# Stack_Rduino-SAMD_V2-PRO_2021-01-03_21-2.net
KiCad netlist of a schematic drawn in Altium Designer
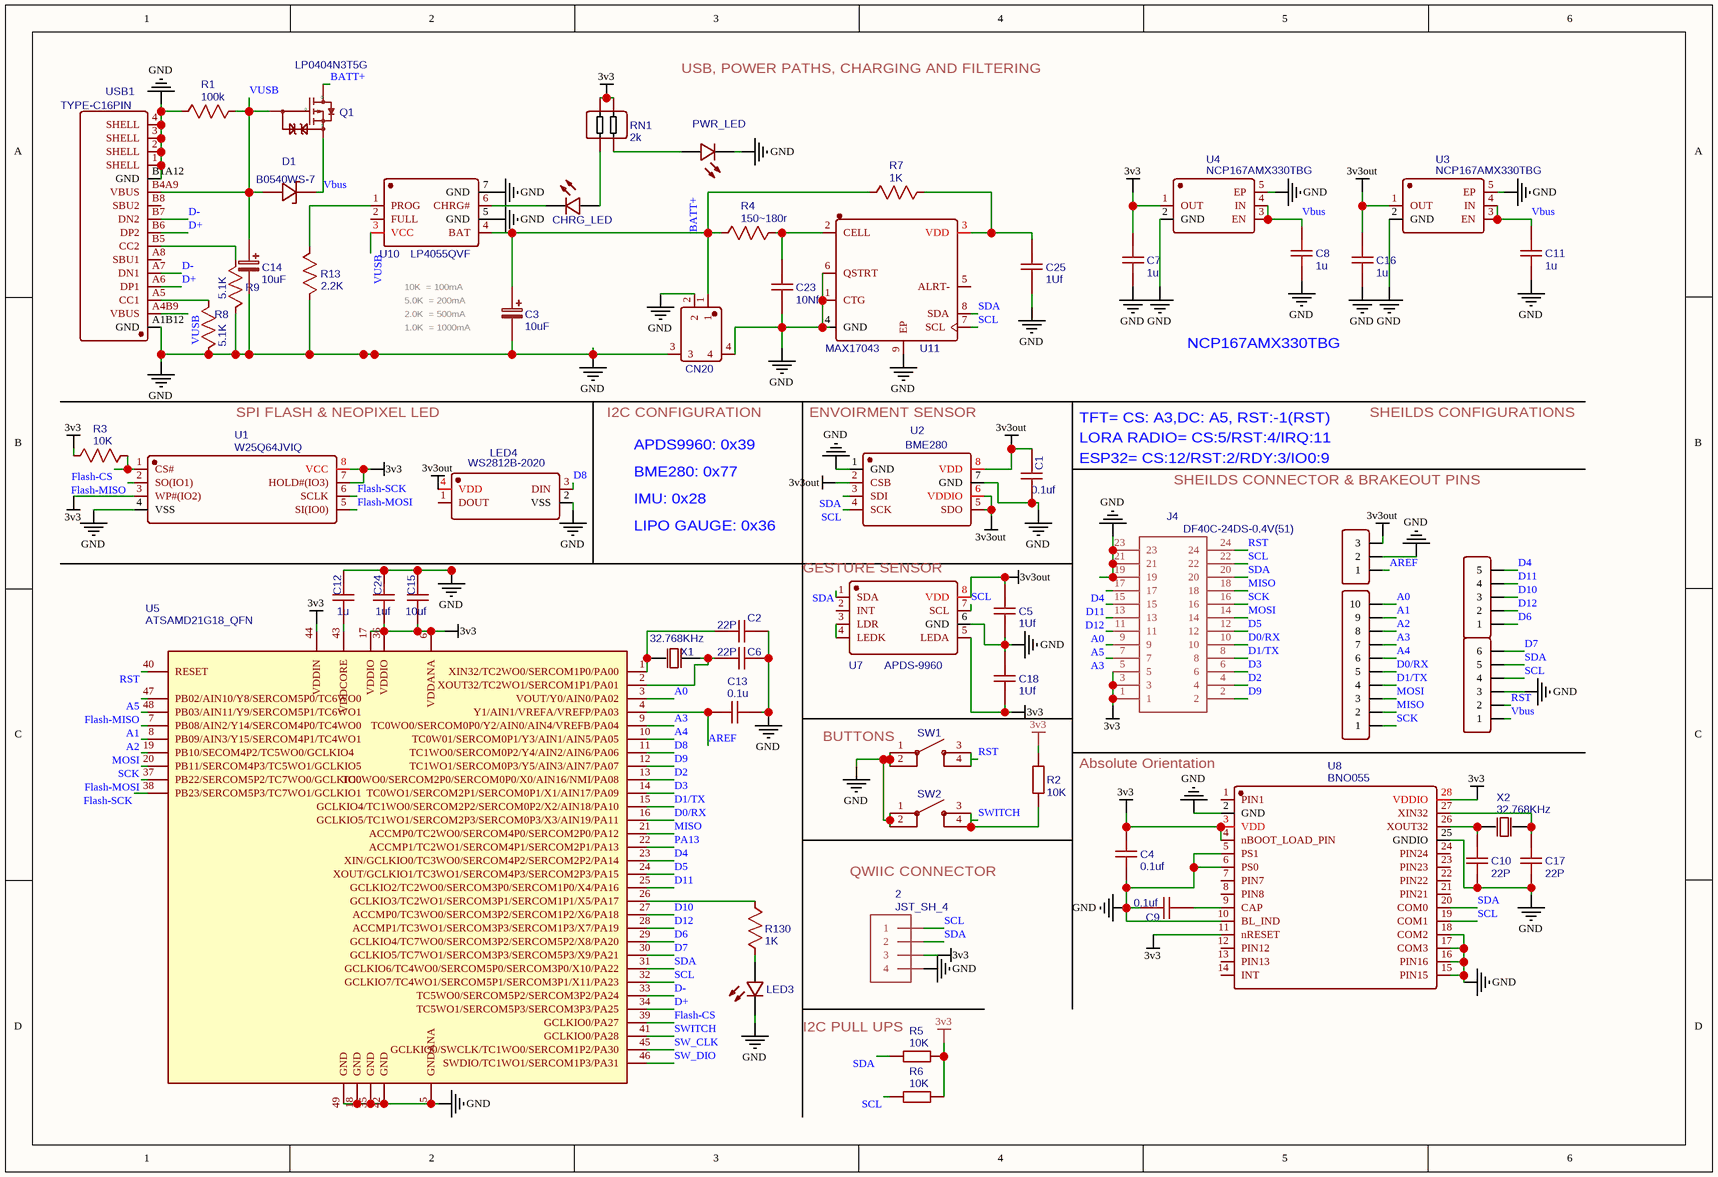
[diagram p0: Stack_Rduino-SAMD_V2-PRO_2021-01-03_21-24-34.schdoc]

(export (version "E")
  (design (tool "Eeschema 10.0.6"))
  (components
    (comp (ref "2")
      (value "JST_SH_4")
      (fields (field (name "CONTRIBUTOR") "guerwood"))
      (libsource (lib "altium-import") (part "root_0_JST_SH_4_"))
    )
    (comp (ref "C1")
      (value "0.1uf")
      (fields (field (name "CONTRIBUTOR") "LCEDA_Lib"))
      (libsource (lib "altium-import") (part "root_3_0.1uf_"))
    )
    (comp (ref "C2")
      (value "22P")
      (fields (field (name "CONTRIBUTOR") "LCEDA_Lib"))
      (libsource (lib "altium-import") (part "root_2_22P_"))
    )
    (comp (ref "C3")
      (value "10uF")
      (fields
        (field (name "BOM_SUPPLIER PART") "C597677")
        (field (name "BOM_MANUFACTURER PART") "TACL106M006XTA")
        (field (name "CONTRIBUTOR") "LCSC")
      )
      (libsource (lib "altium-import") (part "root_1_10uF_"))
    )
    (comp (ref "C4")
      (value "0.1uf")
      (fields (field (name "CONTRIBUTOR") "LCEDA_Lib"))
      (libsource (lib "altium-import") (part "root_1_0.1uf_"))
    )
    (comp (ref "C5")
      (value "1Uf")
      (fields (field (name "CONTRIBUTOR") "LCEDA_Lib"))
      (libsource (lib "altium-import") (part "root_3_1Uf_"))
    )
    (comp (ref "C6")
      (value "22P")
      (fields (field (name "CONTRIBUTOR") "LCEDA_Lib"))
      (libsource (lib "altium-import") (part "root_0_22P_"))
    )
    (comp (ref "C7")
      (value "1u")
      (fields (field (name "CONTRIBUTOR") "LCEDA_Lib"))
      (libsource (lib "altium-import") (part "root_3_1u_"))
    )
    (comp (ref "C8")
      (value "1u")
      (fields (field (name "CONTRIBUTOR") "LCEDA_Lib"))
      (libsource (lib "altium-import") (part "root_3_1u_"))
    )
    (comp (ref "C9")
      (value "0.1uf")
      (fields (field (name "CONTRIBUTOR") "LCEDA_Lib"))
      (libsource (lib "altium-import") (part "root_0_0.1uf_"))
    )
    (comp (ref "C10")
      (value "22P")
      (fields (field (name "CONTRIBUTOR") "LCEDA_Lib"))
      (libsource (lib "altium-import") (part "root_3_22P_"))
    )
    (comp (ref "C11")
      (value "1u")
      (fields (field (name "CONTRIBUTOR") "LCEDA_Lib"))
      (libsource (lib "altium-import") (part "root_3_1u_"))
    )
    (comp (ref "C12")
      (value "1u")
      (fields (field (name "CONTRIBUTOR") "LCEDA_Lib"))
      (libsource (lib "altium-import") (part "root_3_1u_"))
    )
    (comp (ref "C13")
      (value "0.1u")
      (fields (field (name "CONTRIBUTOR") "LCEDA_Lib"))
      (libsource (lib "altium-import") (part "root_2_0.1u_"))
    )
    (comp (ref "C14")
      (value "10uF")
      (fields
        (field (name "BOM_SUPPLIER PART") "C597677")
        (field (name "BOM_MANUFACTURER PART") "TACL106M006XTA")
        (field (name "CONTRIBUTOR") "LCSC")
      )
      (libsource (lib "altium-import") (part "root_1_10uF_"))
    )
    (comp (ref "C15")
      (value "10uf")
      (fields (field (name "CONTRIBUTOR") "LCEDA_Lib"))
      (libsource (lib "altium-import") (part "root_1_10uf_"))
    )
    (comp (ref "C16")
      (value "1u")
      (fields (field (name "CONTRIBUTOR") "LCEDA_Lib"))
      (libsource (lib "altium-import") (part "root_3_1u_"))
    )
    (comp (ref "C17")
      (value "22P")
      (fields (field (name "CONTRIBUTOR") "LCEDA_Lib"))
      (libsource (lib "altium-import") (part "root_1_22P_"))
    )
    (comp (ref "C18")
      (value "1Uf")
      (fields (field (name "CONTRIBUTOR") "LCEDA_Lib"))
      (libsource (lib "altium-import") (part "root_3_1Uf_"))
    )
    (comp (ref "C23")
      (value "10Nf")
      (fields (field (name "CONTRIBUTOR") "LCEDA_Lib"))
      (libsource (lib "altium-import") (part "root_1_10Nf_"))
    )
    (comp (ref "C24")
      (value "1uf")
      (fields (field (name "CONTRIBUTOR") "LCEDA_Lib"))
      (libsource (lib "altium-import") (part "root_1_1uf_"))
    )
    (comp (ref "C25")
      (value "1Uf")
      (fields (field (name "CONTRIBUTOR") "LCEDA_Lib"))
      (libsource (lib "altium-import") (part "root_3_1Uf_"))
    )
    (comp (ref "CHRG_LED")
      (value "Green")
      (fields
        (field (name "BOM_MANUFACTURER PART") "BL-HB337A-AV-TRB")
        (field (name "BOM_SUPPLIER PART") "C165977")
        (field (name "CONTRIBUTOR") "LCSC")
      )
      (libsource (lib "altium-import") (part "root_0_Green_"))
    )
    (comp (ref "CN20")
      (value "A1002WR-S-2P")
      (fields (field (name "BOM_SUPPLIER PART") "C239520") (field (name "CONTRIBUTOR") "LCSC"))
      (libsource (lib "altium-import") (part "root_3_A1002WR-S-2P_"))
    )
    (comp (ref "D1")
      (value "B0540WS-7")
      (fields (field (name "BOM_SUPPLIER PART") "C98664") (field (name "CONTRIBUTOR") "LCSC"))
      (libsource (lib "altium-import") (part "root_2_B0540WS-7_"))
    )
    (comp (ref "H1")
      (value "HDR-F-2.54_1x5")
      (fields (field (name "BOM_SUPPLIER PART") "C50950") (field (name "CONTRIBUTOR") "LCEDA_Lib"))
      (libsource (lib "altium-import") (part "root_2_HDR-F-2.54_1x5_"))
    )
    (comp (ref "H2")
      (value "HDR-F-2.54_1x6")
      (fields (field (name "BOM_SUPPLIER PART") "C40877") (field (name "CONTRIBUTOR") "LCEDA_Lib"))
      (libsource (lib "altium-import") (part "root_2_HDR-F-2.54_1x6_"))
    )
    (comp (ref "H3")
      (value "HDR-F-2.54_1x10")
      (fields (field (name "BOM_SUPPLIER PART") "C35445") (field (name "CONTRIBUTOR") "LCEDA_Lib"))
      (libsource (lib "altium-import") (part "root_2_HDR-F-2.54_1x10_"))
    )
    (comp (ref "J1")
      (value "HDR-M-2.54_1x3")
      (fields (field (name "BOM_SUPPLIER PART") "C180248") (field (name "CONTRIBUTOR") "LCEDA_Lib"))
      (libsource (lib "altium-import") (part "root_2_HDR-M-2.54_1x3_"))
    )
    (comp (ref "J4")
      (value "DF40C-24DS-0.4V(51)")
      (fields (field (name "BOM_SUPPLIER PART") "C424640") (field (name "CONTRIBUTOR") "Hany_elkomy"))
      (libsource (lib "altium-import") (part "root_2_DF40C-24DS-0.4V(51)_"))
    )
    (comp (ref "LED3")
      (value "BL-HB337A-AV-TRB")
      (fields (field (name "BOM_SUPPLIER PART") "C165977") (field (name "CONTRIBUTOR") "LCSC"))
      (libsource (lib "altium-import") (part "root_1_BL-HB337A-AV-TRB_"))
    )
    (comp (ref "LED4")
      (value "WS2812B-2020")
      (fields
        (field (name "BOM_MANUFACTURER PART") "WS2812B")
        (field (name "BOM_SUPPLIER PART") "C114585")
        (field (name "CONTRIBUTOR") "spatz")
      )
      (libsource (lib "altium-import") (part "root_0_WS2812B-2020_"))
    )
    (comp (ref "PWR_LED")
      (value "Red")
      (fields
        (field (name "BOM_MANUFACTURER PART") "BL-HB337A-AV-TRB")
        (field (name "BOM_SUPPLIER PART") "C165977")
        (field (name "CONTRIBUTOR") "LCSC")
      )
      (libsource (lib "altium-import") (part "root_2_Red_"))
    )
    (comp (ref "Q1")
      (value "LP0404N3T5G")
      (fields (field (name "BOM_SUPPLIER PART") "C172433") (field (name "CONTRIBUTOR") "LCSC"))
      (libsource (lib "altium-import") (part "root_0_LP0404N3T5G_"))
    )
    (comp (ref "R1")
      (value "100k")
      (fields (field (name "CONTRIBUTOR") "LCEDA_Lib"))
      (libsource (lib "altium-import") (part "root_0_100k_"))
    )
    (comp (ref "R2")
      (value "10K")
      (fields
        (field (name "BOM_MANUFACTURER PART") "RC0603FR-0739KL")
        (field (name "BOM_SUPPLIER PART") "C163424")
        (field (name "CONTRIBUTOR") "LCSC")
      )
      (libsource (lib "altium-import") (part "root_3_10K_"))
    )
    (comp (ref "R3")
      (value "10K")
      (fields (field (name "CONTRIBUTOR") "LCEDA_Lib"))
      (libsource (lib "") (part "root_2_10K__1"))
    )
    (comp (ref "R4")
      (value "150~180r")
      (fields (field (name "CONTRIBUTOR") "LCEDA_Lib"))
      (libsource (lib "altium-import") (part "root_2_150~180r_"))
    )
    (comp (ref "R5")
      (value "10K")
      (fields
        (field (name "BOM_MANUFACTURER PART") "RC0603FR-0739KL")
        (field (name "BOM_SUPPLIER PART") "C163424")
        (field (name "CONTRIBUTOR") "LCSC")
      )
      (libsource (lib "altium-import") (part "root_2_10K_"))
    )
    (comp (ref "R6")
      (value "10K")
      (fields
        (field (name "BOM_MANUFACTURER PART") "RC0603FR-0739KL")
        (field (name "BOM_SUPPLIER PART") "C163424")
        (field (name "CONTRIBUTOR") "LCSC")
      )
      (libsource (lib "altium-import") (part "root_0_10K_"))
    )
    (comp (ref "R7")
      (value "1K")
      (fields (field (name "CONTRIBUTOR") "LCEDA_Lib"))
      (libsource (lib "altium-import") (part "root_2_1K_"))
    )
    (comp (ref "R8")
      (value "5.1K")
      (fields (field (name "CONTRIBUTOR") "LCEDA_Lib"))
      (libsource (lib "altium-import") (part "root_3_5.1K_"))
    )
    (comp (ref "R9")
      (value "5.1K")
      (fields (field (name "CONTRIBUTOR") "LCEDA_Lib"))
      (libsource (lib "altium-import") (part "root_1_5.1K_"))
    )
    (comp (ref "R13")
      (value "2.2K")
      (fields (field (name "CONTRIBUTOR") "LCEDA_Lib"))
      (libsource (lib "altium-import") (part "root_3_2.2K_"))
    )
    (comp (ref "R130")
      (value "1K")
      (fields (field (name "CONTRIBUTOR") "LCEDA_Lib"))
      (libsource (lib "altium-import") (part "root_3_1K_"))
    )
    (comp (ref "RN1")
      (value "2k")
      (fields
        (field (name "BOM_SUPPLIER PART") "C718251")
        (field (name "BOM_MANUFACTURER PART") "YC122-JR-072K")
        (field (name "CONTRIBUTOR") "LCSC")
      )
      (libsource (lib "altium-import") (part "root_3_2k_"))
    )
    (comp (ref "SW1")
      (value "K2-1177SW-D4DW-06-hany")
      (fields
        (field (name "BOM_SUPPLIER PART") "C223820")
        (field (name "BOM_MANUFACTURER PART") "K2-1177SW-D4DW-06")
        (field (name "CONTRIBUTOR") "Hany_elkomy")
      )
      (libsource (lib "altium-import") (part "root_0_K2-1177SW-D4DW-06-hany_"))
    )
    (comp (ref "SW2")
      (value "K2-1177SW-D4DW-06-hany")
      (fields
        (field (name "BOM_SUPPLIER PART") "C223820")
        (field (name "BOM_MANUFACTURER PART") "K2-1177SW-D4DW-06")
        (field (name "CONTRIBUTOR") "Hany_elkomy")
      )
      (libsource (lib "altium-import") (part "root_0_K2-1177SW-D4DW-06-hany_"))
    )
    (comp (ref "U1")
      (value "W25Q64JVIQ")
      (fields
        (field (name "BOM_SUPPLIER PART") "C395538")
        (field (name "BOM_MANUFACTURER PART") "GD25Q64CQIGR")
        (field (name "CONTRIBUTOR") "LCSC")
      )
      (libsource (lib "altium-import") (part "root_0_W25Q64JVIQ_"))
    )
    (comp (ref "U2")
      (value "BME280")
      (fields (field (name "BOM_SUPPLIER PART") "C92489") (field (name "CONTRIBUTOR") "LCSC"))
      (libsource (lib "altium-import") (part "root_0_BME280_"))
    )
    (comp (ref "U3")
      (value "NCP167AMX330TBG")
      (fields
        (field (name "BOM_MANUFACTURER PART") "NCP170AMX300TCG")
        (field (name "BOM_SUPPLIER PART") "C152284")
        (field (name "CONTRIBUTOR") "LCSC")
      )
      (libsource (lib "altium-import") (part "root_0_NCP167AMX330TBG_"))
    )
    (comp (ref "U4")
      (value "NCP167AMX330TBG")
      (fields
        (field (name "BOM_MANUFACTURER PART") "NCP170AMX300TCG")
        (field (name "BOM_SUPPLIER PART") "C152284")
        (field (name "CONTRIBUTOR") "LCSC")
      )
      (libsource (lib "altium-import") (part "root_0_NCP167AMX330TBG_"))
    )
    (comp (ref "U5")
      (value "ATSAMD21G18_QFN")
      (fields (field (name "CONTRIBUTOR") "corlovsky"))
      (libsource (lib "altium-import") (part "root_0_ATSAMD21G18_QFN_"))
    )
    (comp (ref "U7")
      (value "APDS-9960")
      (fields (field (name "BOM_SUPPLIER PART") "C93222") (field (name "CONTRIBUTOR") "LCSC"))
      (libsource (lib "altium-import") (part "root_0_APDS-9960_"))
    )
    (comp (ref "U8")
      (value "BNO055")
      (fields (field (name "BOM_SUPPLIER PART") "C93216") (field (name "CONTRIBUTOR") "LCSC"))
      (libsource (lib "altium-import") (part "root_0_BNO055_"))
    )
    (comp (ref "U10")
      (value "LP4055QVF")
      (fields (field (name "BOM_SUPPLIER PART") "C387714") (field (name "CONTRIBUTOR") "LCSC"))
      (libsource (lib "altium-import") (part "root_0_LP4055QVF_"))
    )
    (comp (ref "U11")
      (value "MAX17043")
      (fields (field (name "BOM_MANUFACTURER PART") "MAX17043G+U") (field (name "CONTRIBUTOR") "whatski"))
      (libsource (lib "altium-import") (part "root_0_MAX17043_"))
    )
    (comp (ref "USB1")
      (value "TYPE-C16PIN")
      (fields (field (name "BOM_SUPPLIER PART") "C393939") (field (name "CONTRIBUTOR") "LCSC"))
      (libsource (lib "altium-import") (part "root_2_TYPE-C16PIN_"))
    )
    (comp (ref "X1")
      (value "32.768KHz")
      (fields
        (field (name "BOM_MANUFACTURER PART") "FC-12M32.768KHZ7PF20PPM")
        (field (name "BOM_SUPPLIER PART") "C99009")
      )
      (libsource (lib "altium-import") (part "root_0_32.768KHz_"))
    )
    (comp (ref "X2")
      (value "32.768KHz")
      (fields
        (field (name "BOM_MANUFACTURER PART") "FC-12M32.768KHZ7PF20PPM")
        (field (name "BOM_SUPPLIER PART") "C99009")
      )
      (libsource (lib "altium-import") (part "root_0_32.768KHz_"))
    )
  )
  (nets
    (net (code "1") (name "/A0") (class "Default")
      (node (ref "H3") (pin "10") (pinfunction "10_10") (pintype "passive"))
      (node (ref "J4") (pin "11") (pinfunction "11_11") (pintype "passive"))
      (node (ref "U5") (pin "3") (pinfunction "VOUT/Y0/AIN0/PA02_3") (pintype "passive"))
    )
    (net (code "2") (name "/A1") (class "Default")
      (node (ref "H3") (pin "9") (pinfunction "9_9") (pintype "passive"))
      (node (ref "U5") (pin "7") (pinfunction "PB08/AIN2/Y14/SERCOM4P0/TC4WO0_7") (pintype "passive"))
    )
    (net (code "3") (name "/A2") (class "Default")
      (node (ref "H3") (pin "8") (pinfunction "8_8") (pintype "passive"))
      (node (ref "U5") (pin "8") (pinfunction "PB09/AIN3/Y15/SERCOM4P1/TC4WO1_8") (pintype "passive"))
    )
    (net (code "4") (name "/A3") (class "Default")
      (node (ref "H3") (pin "7") (pinfunction "7_7") (pintype "passive"))
      (node (ref "J4") (pin "7") (pinfunction "7_7") (pintype "passive"))
      (node (ref "U5") (pin "9") (pinfunction "TC0WO0/SERCOM0P0/Y2/AIN0/AIN4/VREFB/PA04_9") (pintype "passive"))
    )
    (net (code "5") (name "/A4") (class "Default")
      (node (ref "H3") (pin "6") (pinfunction "6_6") (pintype "passive"))
      (node (ref "U5") (pin "10") (pinfunction "TC0W01/SERCOM0P1/Y3/AIN1/AIN5/PA05_10") (pintype "passive"))
    )
    (net (code "6") (name "/A5") (class "Default")
      (node (ref "J4") (pin "9") (pinfunction "9_9") (pintype "passive"))
      (node (ref "U5") (pin "47") (pinfunction "PB02/AIN10/Y8/SERCOM5P0/TC6WO0_47") (pintype "passive"))
    )
    (net (code "7") (name "/AREF") (class "Default")
      (node (ref "C13") (pin "2") (pinfunction "2_2") (pintype "passive"))
      (node (ref "J1") (pin "1") (pinfunction "1_1") (pintype "passive"))
      (node (ref "U5") (pin "4") (pinfunction "Y1/AIN1/VREFA/VREFP/PA03_4") (pintype "passive"))
    )
    (net (code "8") (name "/BATT+") (class "Default")
      (node (ref "C3") (pin "1") (pinfunction "1_1") (pintype "passive"))
      (node (ref "CN20") (pin "1") (pinfunction "1_1") (pintype "passive"))
      (node (ref "Q1") (pin "3") (pinfunction "D_3") (pintype "passive"))
      (node (ref "R4") (pin "2") (pinfunction "2_2") (pintype "passive"))
      (node (ref "R7") (pin "2") (pinfunction "2_2") (pintype "passive"))
      (node (ref "U10") (pin "4") (pinfunction "BAT_4") (pintype "passive"))
    )
    (net (code "9") (name "/D+") (class "Default")
      (node (ref "U5") (pin "34") (pinfunction "TC5WO1/SERCOM5P3/SERCOM3P3/PA25_34") (pintype "passive"))
      (node (ref "USB1") (pin "A6") (pinfunction "DP1_A6") (pintype "passive"))
      (node (ref "USB1") (pin "B6") (pinfunction "DP2_B6") (pintype "passive"))
    )
    (net (code "10") (name "/D-") (class "Default")
      (node (ref "U5") (pin "33") (pinfunction "TC5WO0/SERCOM5P2/SERCOM3P2/PA24_33") (pintype "passive"))
      (node (ref "USB1") (pin "A7") (pinfunction "DN1_A7") (pintype "passive"))
      (node (ref "USB1") (pin "B7") (pinfunction "DN2_B7") (pintype "passive"))
    )
    (net (code "11") (name "/D0{slash}RX") (class "Default")
      (node (ref "H3") (pin "5") (pinfunction "5_5") (pintype "passive"))
      (node (ref "J4") (pin "10") (pinfunction "10_10") (pintype "passive"))
      (node (ref "U5") (pin "16") (pinfunction "GCLKIO5/TC1WO1/SERCOM2P3/SERCOM0P3/X3/AIN19/PA11_16") (pintype "passive"))
    )
    (net (code "12") (name "/D1{slash}TX") (class "Default")
      (node (ref "H3") (pin "4") (pinfunction "4_4") (pintype "passive"))
      (node (ref "J4") (pin "8") (pinfunction "8_8") (pintype "passive"))
      (node (ref "U5") (pin "15") (pinfunction "GCLKIO4/TC1WO0/SERCOM2P2/SERCOM0P2/X2/AIN18/PA10_15") (pintype "passive"))
    )
    (net (code "13") (name "/D2") (class "Default")
      (node (ref "J4") (pin "4") (pinfunction "4_4") (pintype "passive"))
      (node (ref "U5") (pin "13") (pinfunction "TC0WO0/SERCOM2P0/SERCOM0P0/X0/AIN16/NMI/PA08_13") (pintype "passive"))
    )
    (net (code "14") (name "/D3") (class "Default")
      (node (ref "J4") (pin "6") (pinfunction "6_6") (pintype "passive"))
      (node (ref "U5") (pin "14") (pinfunction "TC0WO1/SERCOM2P1/SERCOM0P1/X1/AIN17/PA09_14") (pintype "passive"))
    )
    (net (code "15") (name "/D4") (class "Default")
      (node (ref "H1") (pin "5") (pinfunction "5_5") (pintype "passive"))
      (node (ref "J4") (pin "17") (pinfunction "17_17") (pintype "passive"))
      (node (ref "U5") (pin "23") (pinfunction "XIN/GCLKIO0/TC3WO0/SERCOM4P2/SERCOM2P2/PA14_23") (pintype "passive"))
    )
    (net (code "16") (name "/D5") (class "Default")
      (node (ref "J4") (pin "12") (pinfunction "12_12") (pintype "passive"))
      (node (ref "U5") (pin "24") (pinfunction "XOUT/GCLKIO1/TC3WO1/SERCOM4P3/SERCOM2P3/PA15_24") (pintype "passive"))
    )
    (net (code "17") (name "/D6") (class "Default")
      (node (ref "H1") (pin "1") (pinfunction "1_1") (pintype "passive"))
      (node (ref "U5") (pin "29") (pinfunction "GCLKIO4/TC7WO0/SERCOM3P2/SERCOM5P2/X8/PA20_29") (pintype "passive"))
    )
    (net (code "18") (name "/D7") (class "Default")
      (node (ref "H2") (pin "6") (pinfunction "6_6") (pintype "passive"))
      (node (ref "U5") (pin "30") (pinfunction "GCLKIO5/TC7WO1/SERCOM3P3/SERCOM5P3/X9/PA21_30") (pintype "passive"))
    )
    (net (code "19") (name "/D8") (class "Default")
      (node (ref "LED4") (pin "3") (pinfunction "DIN_3") (pintype "passive"))
      (node (ref "U5") (pin "11") (pinfunction "TC1WO0/SERCOM0P2/Y4/AIN2/AIN6/PA06_11") (pintype "passive"))
    )
    (net (code "20") (name "/D9") (class "Default")
      (node (ref "J4") (pin "2") (pinfunction "2_2") (pintype "passive"))
      (node (ref "U5") (pin "12") (pinfunction "TC1WO1/SERCOM0P3/Y5/AIN3/AIN7/PA07_12") (pintype "passive"))
    )
    (net (code "21") (name "/D10") (class "Default")
      (node (ref "H1") (pin "3") (pinfunction "3_3") (pintype "passive"))
      (node (ref "U5") (pin "27") (pinfunction "ACCMP0/TC3WO0/SERCOM3P2/SERCOM1P2/X6/PA18_27") (pintype "passive"))
    )
    (net (code "22") (name "/D11") (class "Default")
      (node (ref "H1") (pin "4") (pinfunction "4_4") (pintype "passive"))
      (node (ref "J4") (pin "15") (pinfunction "15_15") (pintype "passive"))
      (node (ref "U5") (pin "25") (pinfunction "GCLKIO2/TC2WO0/SERCOM3P0/SERCOM1P0/X4/PA16_25") (pintype "passive"))
    )
    (net (code "23") (name "/D12") (class "Default")
      (node (ref "H1") (pin "2") (pinfunction "2_2") (pintype "passive"))
      (node (ref "J4") (pin "13") (pinfunction "13_13") (pintype "passive"))
      (node (ref "U5") (pin "28") (pinfunction "ACCMP1/TC3WO1/SERCOM3P3/SERCOM1P3/X7/PA19_28") (pintype "passive"))
    )
    (net (code "24") (name "/Flash-CS") (class "Default")
      (node (ref "R3") (pin "1") (pinfunction "1_1") (pintype "passive"))
      (node (ref "U1") (pin "1") (pinfunction "CS#_1") (pintype "passive"))
      (node (ref "U5") (pin "39") (pinfunction "GCLKIO0/PA27_39") (pintype "passive"))
    )
    (net (code "25") (name "/Flash-MISO") (class "Default")
      (node (ref "U1") (pin "2") (pinfunction "SO(IO1)_2") (pintype "passive"))
      (node (ref "U5") (pin "48") (pinfunction "PB03/AIN11/Y9/SERCOM5P1/TC6WO1_48") (pintype "passive"))
    )
    (net (code "26") (name "/Flash-MOSI") (class "Default")
      (node (ref "U1") (pin "5") (pinfunction "SI(IO0)_5") (pintype "passive"))
      (node (ref "U5") (pin "37") (pinfunction "PB22/SERCOM5P2/TC7WO0/GCLKIO0_37") (pintype "passive"))
    )
    (net (code "27") (name "/Flash-SCK") (class "Default")
      (node (ref "U1") (pin "6") (pinfunction "SCLK_6") (pintype "passive"))
      (node (ref "U5") (pin "38") (pinfunction "PB23/SERCOM5P3/TC7WO1/GCLKIO1_38") (pintype "passive"))
    )
    (net (code "28") (name "/MISO") (class "Default")
      (node (ref "H3") (pin "2") (pinfunction "2_2") (pintype "passive"))
      (node (ref "J4") (pin "18") (pinfunction "18_18") (pintype "passive"))
      (node (ref "U5") (pin "21") (pinfunction "ACCMP0/TC2WO0/SERCOM4P0/SERCOM2P0/PA12_21") (pintype "passive"))
    )
    (net (code "29") (name "/MOSI") (class "Default")
      (node (ref "H3") (pin "3") (pinfunction "3_3") (pintype "passive"))
      (node (ref "J4") (pin "14") (pinfunction "14_14") (pintype "passive"))
      (node (ref "U5") (pin "19") (pinfunction "PB10/SECOM4P2/TC5WO0/GCLKIO4_19") (pintype "passive"))
    )
    (net (code "30") (name "/PA13") (class "Default")
      (node (ref "U5") (pin "22") (pinfunction "ACCMP1/TC2WO1/SERCOM4P1/SERCOM2P1/PA13_22") (pintype "passive"))
    )
    (net (code "31") (name "/RST") (class "Default")
      (node (ref "H2") (pin "2") (pinfunction "2_2") (pintype "passive"))
      (node (ref "J4") (pin "24") (pinfunction "24_24") (pintype "passive"))
      (node (ref "SW1") (pin "3") (pinfunction "3_3") (pintype "passive"))
      (node (ref "SW1") (pin "4") (pinfunction "4_4") (pintype "passive"))
      (node (ref "U5") (pin "40") (pinfunction "RESET_40") (pintype "passive"))
    )
    (net (code "32") (name "/SCK") (class "Default")
      (node (ref "H3") (pin "1") (pinfunction "1_1") (pintype "passive"))
      (node (ref "J4") (pin "16") (pinfunction "16_16") (pintype "passive"))
      (node (ref "U5") (pin "20") (pinfunction "PB11/SERCOM4P3/TC5WO1/GCLKIO5_20") (pintype "passive"))
    )
    (net (code "33") (name "/SCL") (class "Default")
      (node (ref "2") (pin "1") (pinfunction "1_1") (pintype "passive"))
      (node (ref "H2") (pin "4") (pinfunction "4_4") (pintype "passive"))
      (node (ref "J4") (pin "22") (pinfunction "22_22") (pintype "passive"))
      (node (ref "R6") (pin "1") (pinfunction "1_1") (pintype "passive"))
      (node (ref "U11") (pin "7") (pinfunction "SCL_7") (pintype "passive"))
      (node (ref "U2") (pin "4") (pinfunction "SCK_4") (pintype "passive"))
      (node (ref "U5") (pin "32") (pinfunction "GCLKIO7/TC4WO1/SERCOM5P1/SERCOM3P1/X11/PA23_32") (pintype "passive"))
      (node (ref "U7") (pin "7") (pinfunction "SCL_7") (pintype "passive"))
      (node (ref "U8") (pin "19") (pinfunction "COM1_19") (pintype "passive"))
    )
    (net (code "34") (name "/SDA") (class "Default")
      (node (ref "2") (pin "2") (pinfunction "2_2") (pintype "passive"))
      (node (ref "H2") (pin "5") (pinfunction "5_5") (pintype "passive"))
      (node (ref "J4") (pin "20") (pinfunction "20_20") (pintype "passive"))
      (node (ref "R5") (pin "2") (pinfunction "2_2") (pintype "passive"))
      (node (ref "U11") (pin "8") (pinfunction "SDA_8") (pintype "passive"))
      (node (ref "U2") (pin "3") (pinfunction "SDI_3") (pintype "passive"))
      (node (ref "U5") (pin "31") (pinfunction "GCLKIO6/TC4WO0/SERCOM5P0/SERCOM3P0/X10/PA22_31") (pintype "passive"))
      (node (ref "U7") (pin "1") (pinfunction "SDA_1") (pintype "passive"))
      (node (ref "U8") (pin "20") (pinfunction "COM0_20") (pintype "passive"))
    )
    (net (code "35") (name "/SWITCH") (class "Default")
      (node (ref "R2") (pin "2") (pinfunction "2_2") (pintype "passive"))
      (node (ref "SW2") (pin "3") (pinfunction "3_3") (pintype "passive"))
      (node (ref "SW2") (pin "4") (pinfunction "4_4") (pintype "passive"))
      (node (ref "U5") (pin "41") (pinfunction "GCLKIO0/PA28_41") (pintype "passive"))
    )
    (net (code "36") (name "/SW_CLK") (class "Default")
      (node (ref "U5") (pin "45") (pinfunction "GCLKIO0/SWCLK/TC1WO0/SERCOM1P2/PA30_45") (pintype "passive"))
    )
    (net (code "37") (name "/SW_DIO") (class "Default")
      (node (ref "U5") (pin "46") (pinfunction "SWDIO/TC1WO1/SERCOM1P3/PA31_46") (pintype "passive"))
    )
    (net (code "38") (name "/VUSB") (class "Default")
      (node (ref "C14") (pin "1") (pinfunction "1_1") (pintype "passive"))
      (node (ref "D1") (pin "2") (pinfunction "A_2") (pintype "passive"))
      (node (ref "Q1") (pin "1") (pinfunction "G_1") (pintype "passive"))
      (node (ref "R1") (pin "2") (pinfunction "2_2") (pintype "passive"))
      (node (ref "U10") (pin "3") (pinfunction "VCC_3") (pintype "passive"))
      (node (ref "USB1") (pin "A4B9") (pinfunction "VBUS_A4B9") (pintype "passive"))
      (node (ref "USB1") (pin "B4A9") (pinfunction "VBUS_B4A9") (pintype "passive"))
    )
    (net (code "39") (name "/Vbus") (class "Default")
      (node (ref "C11") (pin "1") (pinfunction "1_1") (pintype "passive"))
      (node (ref "C8") (pin "1") (pinfunction "1_1") (pintype "passive"))
      (node (ref "D1") (pin "1") (pinfunction "C_1") (pintype "passive"))
      (node (ref "H2") (pin "1") (pinfunction "1_1") (pintype "passive"))
      (node (ref "Q1") (pin "2") (pinfunction "S_2") (pintype "passive"))
      (node (ref "U3") (pin "3") (pinfunction "EN_3") (pintype "passive"))
      (node (ref "U3") (pin "4") (pinfunction "IN_4") (pintype "passive"))
      (node (ref "U4") (pin "3") (pinfunction "EN_3") (pintype "passive"))
      (node (ref "U4") (pin "4") (pinfunction "IN_4") (pintype "passive"))
    )
    (net (code "40") (name "3v3") (class "Default")
      (node (ref "2") (pin "3") (pinfunction "3_3") (pintype "passive"))
      (node (ref "C15") (pin "1") (pinfunction "1_1") (pintype "passive"))
      (node (ref "C18") (pin "2") (pinfunction "2_2") (pintype "passive"))
      (node (ref "C24") (pin "1") (pinfunction "1_1") (pintype "passive"))
      (node (ref "C4") (pin "2") (pinfunction "2_2") (pintype "passive"))
      (node (ref "C7") (pin "1") (pinfunction "1_1") (pintype "passive"))
      (node (ref "J4") (pin "1") (pinfunction "1_1") (pintype "passive"))
      (node (ref "J4") (pin "3") (pinfunction "3_3") (pintype "passive"))
      (node (ref "J4") (pin "5") (pinfunction "5_5") (pintype "passive"))
      (node (ref "R2") (pin "1") (pinfunction "1_1") (pintype "passive"))
      (node (ref "R3") (pin "2") (pinfunction "2_2") (pintype "passive"))
      (node (ref "R5") (pin "1") (pinfunction "1_1") (pintype "passive"))
      (node (ref "R6") (pin "2") (pinfunction "2_2") (pintype "passive"))
      (node (ref "RN1") (pin "1") (pinfunction "1_1") (pintype "passive"))
      (node (ref "RN1") (pin "2") (pinfunction "2_2") (pintype "passive"))
      (node (ref "U1") (pin "3") (pinfunction "WP#(IO2)_3") (pintype "passive"))
      (node (ref "U1") (pin "7") (pinfunction "HOLD#(IO3)_7") (pintype "passive"))
      (node (ref "U1") (pin "8") (pinfunction "VCC_8") (pintype "passive"))
      (node (ref "U4") (pin "1") (pinfunction "OUT_1") (pintype "passive"))
      (node (ref "U5") (pin "17") (pinfunction "VDDIO_17") (pintype "passive"))
      (node (ref "U5") (pin "36") (pinfunction "VDDIO_36") (pintype "passive"))
      (node (ref "U5") (pin "44") (pinfunction "VDDIN_44") (pintype "passive"))
      (node (ref "U5") (pin "6") (pinfunction "VDDANA_6") (pintype "passive"))
      (node (ref "U7") (pin "5") (pinfunction "LEDA_5") (pintype "passive"))
      (node (ref "U8") (pin "11") (pinfunction "nRESET_11") (pintype "passive"))
      (node (ref "U8") (pin "28") (pinfunction "VDDIO_28") (pintype "passive"))
      (node (ref "U8") (pin "3") (pinfunction "VDD_3") (pintype "passive"))
      (node (ref "U8") (pin "4") (pinfunction "nBOOT_LOAD_PIN_4") (pintype "passive"))
    )
    (net (code "41") (name "3v3out") (class "Default")
      (node (ref "C1") (pin "1") (pinfunction "1_1") (pintype "passive"))
      (node (ref "C16") (pin "1") (pinfunction "1_1") (pintype "passive"))
      (node (ref "C5") (pin "1") (pinfunction "1_1") (pintype "passive"))
      (node (ref "J1") (pin "3") (pinfunction "3_3") (pintype "passive"))
      (node (ref "LED4") (pin "4") (pinfunction "VDD_4") (pintype "passive"))
      (node (ref "U2") (pin "2") (pinfunction "CSB_2") (pintype "passive"))
      (node (ref "U2") (pin "5") (pinfunction "SDO_5") (pintype "passive"))
      (node (ref "U2") (pin "6") (pinfunction "VDDIO_6") (pintype "passive"))
      (node (ref "U2") (pin "8") (pinfunction "VDD_8") (pintype "passive"))
      (node (ref "U3") (pin "1") (pinfunction "OUT_1") (pintype "passive"))
      (node (ref "U7") (pin "8") (pinfunction "VDD_8") (pintype "passive"))
    )
    (net (code "42") (name "GND") (class "Default")
      (node (ref "2") (pin "4") (pinfunction "4_4") (pintype "passive"))
      (node (ref "C1") (pin "2") (pinfunction "2_2") (pintype "passive"))
      (node (ref "C10") (pin "2") (pinfunction "2_2") (pintype "passive"))
      (node (ref "C11") (pin "2") (pinfunction "2_2") (pintype "passive"))
      (node (ref "C12") (pin "1") (pinfunction "1_1") (pintype "passive"))
      (node (ref "C13") (pin "1") (pinfunction "1_1") (pintype "passive"))
      (node (ref "C14") (pin "2") (pinfunction "2_2") (pintype "passive"))
      (node (ref "C15") (pin "2") (pinfunction "2_2") (pintype "passive"))
      (node (ref "C16") (pin "2") (pinfunction "2_2") (pintype "passive"))
      (node (ref "C17") (pin "1") (pinfunction "1_1") (pintype "passive"))
      (node (ref "C18") (pin "1") (pinfunction "1_1") (pintype "passive"))
      (node (ref "C2") (pin "1") (pinfunction "1_1") (pintype "passive"))
      (node (ref "C23") (pin "1") (pinfunction "1_1") (pintype "passive"))
      (node (ref "C24") (pin "2") (pinfunction "2_2") (pintype "passive"))
      (node (ref "C25") (pin "2") (pinfunction "2_2") (pintype "passive"))
      (node (ref "C3") (pin "2") (pinfunction "2_2") (pintype "passive"))
      (node (ref "C4") (pin "1") (pinfunction "1_1") (pintype "passive"))
      (node (ref "C5") (pin "2") (pinfunction "2_2") (pintype "passive"))
      (node (ref "C6") (pin "2") (pinfunction "2_2") (pintype "passive"))
      (node (ref "C7") (pin "2") (pinfunction "2_2") (pintype "passive"))
      (node (ref "C8") (pin "2") (pinfunction "2_2") (pintype "passive"))
      (node (ref "C9") (pin "1") (pinfunction "1_1") (pintype "passive"))
      (node (ref "CN20") (pin "2") (pinfunction "2_2") (pintype "passive"))
      (node (ref "CN20") (pin "3") (pinfunction "3_3") (pintype "passive"))
      (node (ref "CN20") (pin "4") (pinfunction "4_4") (pintype "passive"))
      (node (ref "H2") (pin "3") (pinfunction "3_3") (pintype "passive"))
      (node (ref "J1") (pin "2") (pinfunction "2_2") (pintype "passive"))
      (node (ref "J4") (pin "19") (pinfunction "19_19") (pintype "passive"))
      (node (ref "J4") (pin "21") (pinfunction "21_21") (pintype "passive"))
      (node (ref "J4") (pin "23") (pinfunction "23_23") (pintype "passive"))
      (node (ref "LED3") (pin "1") (pinfunction "K_1") (pintype "passive"))
      (node (ref "LED4") (pin "2") (pinfunction "VSS_2") (pintype "passive"))
      (node (ref "PWR_LED") (pin "1") (pinfunction "K_1") (pintype "passive"))
      (node (ref "R1") (pin "1") (pinfunction "1_1") (pintype "passive"))
      (node (ref "R13") (pin "2") (pinfunction "2_2") (pintype "passive"))
      (node (ref "R8") (pin "2") (pinfunction "2_2") (pintype "passive"))
      (node (ref "R9") (pin "1") (pinfunction "1_1") (pintype "passive"))
      (node (ref "SW1") (pin "1") (pinfunction "1_1") (pintype "passive"))
      (node (ref "SW1") (pin "2") (pinfunction "2_2") (pintype "passive"))
      (node (ref "SW2") (pin "1") (pinfunction "1_1") (pintype "passive"))
      (node (ref "SW2") (pin "2") (pinfunction "2_2") (pintype "passive"))
      (node (ref "U1") (pin "4") (pinfunction "VSS_4") (pintype "passive"))
      (node (ref "U10") (pin "5") (pinfunction "GND_5") (pintype "passive"))
      (node (ref "U10") (pin "7") (pinfunction "GND_7") (pintype "passive"))
      (node (ref "U11") (pin "1") (pinfunction "CTG_1") (pintype "passive"))
      (node (ref "U11") (pin "4") (pinfunction "GND_4") (pintype "passive"))
      (node (ref "U11") (pin "6") (pinfunction "QSTRT_6") (pintype "passive"))
      (node (ref "U11") (pin "9") (pinfunction "EP_9") (pintype "passive"))
      (node (ref "U2") (pin "1") (pinfunction "GND_1") (pintype "passive"))
      (node (ref "U2") (pin "7") (pinfunction "GND_7") (pintype "passive"))
      (node (ref "U3") (pin "2") (pinfunction "GND_2") (pintype "passive"))
      (node (ref "U3") (pin "5") (pinfunction "EP_5") (pintype "passive"))
      (node (ref "U4") (pin "2") (pinfunction "GND_2") (pintype "passive"))
      (node (ref "U4") (pin "5") (pinfunction "EP_5") (pintype "passive"))
      (node (ref "U5") (pin "18") (pinfunction "GND_18") (pintype "passive"))
      (node (ref "U5") (pin "35") (pinfunction "GND_35") (pintype "passive"))
      (node (ref "U5") (pin "42") (pinfunction "GND_42") (pintype "passive"))
      (node (ref "U5") (pin "49") (pinfunction "GND_49") (pintype "passive"))
      (node (ref "U5") (pin "5") (pinfunction "GNDANA_5") (pintype "passive"))
      (node (ref "U7") (pin "6") (pinfunction "GND_6") (pintype "passive"))
      (node (ref "U8") (pin "10") (pinfunction "BL_IND_10") (pintype "passive"))
      (node (ref "U8") (pin "15") (pinfunction "PIN15_15") (pintype "passive"))
      (node (ref "U8") (pin "16") (pinfunction "PIN16_16") (pintype "passive"))
      (node (ref "U8") (pin "17") (pinfunction "COM3_17") (pintype "passive"))
      (node (ref "U8") (pin "18") (pinfunction "COM2_18") (pintype "passive"))
      (node (ref "U8") (pin "2") (pinfunction "GND_2") (pintype "passive"))
      (node (ref "U8") (pin "25") (pinfunction "GNDIO_25") (pintype "passive"))
      (node (ref "U8") (pin "5") (pinfunction "PS1_5") (pintype "passive"))
      (node (ref "U8") (pin "6") (pinfunction "PS0_6") (pintype "passive"))
      (node (ref "USB1") (pin "1") (pinfunction "SHELL_1") (pintype "passive"))
      (node (ref "USB1") (pin "2") (pinfunction "SHELL_2") (pintype "passive"))
      (node (ref "USB1") (pin "3") (pinfunction "SHELL_3") (pintype "passive"))
      (node (ref "USB1") (pin "4") (pinfunction "SHELL_4") (pintype "passive"))
      (node (ref "USB1") (pin "A1B12") (pinfunction "GND_A1B12") (pintype "passive"))
      (node (ref "USB1") (pin "B1A12") (pinfunction "GND_B1A12") (pintype "passive"))
    )
    (net (code "43") (name "Net-(CHRG_LED-A)") (class "Default")
      (node (ref "CHRG_LED") (pin "2") (pinfunction "A_2") (pintype "passive"))
      (node (ref "RN1") (pin "3") (pinfunction "3_3") (pintype "passive"))
    )
    (net (code "44") (name "Net-(CHRG_LED-K)") (class "Default")
      (node (ref "CHRG_LED") (pin "1") (pinfunction "K_1") (pintype "passive"))
      (node (ref "U10") (pin "6") (pinfunction "CHRG#_6") (pintype "passive"))
    )
    (net (code "45") (name "Net-(LED3-A)") (class "Default")
      (node (ref "LED3") (pin "2") (pinfunction "A_2") (pintype "passive"))
      (node (ref "R130") (pin "2") (pinfunction "2_2") (pintype "passive"))
    )
    (net (code "46") (name "Net-(PWR_LED-A)") (class "Default")
      (node (ref "PWR_LED") (pin "2") (pinfunction "A_2") (pintype "passive"))
      (node (ref "RN1") (pin "4") (pinfunction "4_4") (pintype "passive"))
    )
    (net (code "47") (name "Net-(U5-GCLKIO3{slash}TC2WO1{slash}SERCOM3P1{slash}SERCOM1P1{slash}X5{slash}PA17)") (class "Default")
      (node (ref "R130") (pin "1") (pinfunction "1_1") (pintype "passive"))
      (node (ref "U5") (pin "26") (pinfunction "GCLKIO3/TC2WO1/SERCOM3P1/SERCOM1P1/X5/PA17_26") (pintype "passive"))
    )
    (net (code "48") (name "Net-(U5-VDDCORE)") (class "Default")
      (node (ref "C12") (pin "2") (pinfunction "2_2") (pintype "passive"))
      (node (ref "U5") (pin "43") (pinfunction "VDDCORE_43") (pintype "passive"))
    )
    (net (code "49") (name "Net-(U5-XIN32{slash}TC2WO0{slash}SERCOM1P0{slash}PA00)") (class "Default")
      (node (ref "C2") (pin "2") (pinfunction "2_2") (pintype "passive"))
      (node (ref "U5") (pin "1") (pinfunction "XIN32/TC2WO0/SERCOM1P0/PA00_1") (pintype "passive"))
      (node (ref "X1") (pin "1") (pinfunction "OSC1_1") (pintype "passive"))
    )
    (net (code "50") (name "Net-(U5-XOUT32{slash}TC2WO1{slash}SERCOM1P1{slash}PA01)") (class "Default")
      (node (ref "C6") (pin "1") (pinfunction "1_1") (pintype "passive"))
      (node (ref "U5") (pin "2") (pinfunction "XOUT32/TC2WO1/SERCOM1P1/PA01_2") (pintype "passive"))
      (node (ref "X1") (pin "2") (pinfunction "OSC2_2") (pintype "passive"))
    )
    (net (code "51") (name "Net-(U7-LDR)") (class "Default")
      (node (ref "U7") (pin "3") (pinfunction "LDR_3") (pintype "passive"))
      (node (ref "U7") (pin "4") (pinfunction "LEDK_4") (pintype "passive"))
    )
    (net (code "52") (name "Net-(U8-CAP)") (class "Default")
      (node (ref "C9") (pin "2") (pinfunction "2_2") (pintype "passive"))
      (node (ref "U8") (pin "9") (pinfunction "CAP_9") (pintype "passive"))
    )
    (net (code "53") (name "Net-(U8-XIN32)") (class "Default")
      (node (ref "C17") (pin "2") (pinfunction "2_2") (pintype "passive"))
      (node (ref "U8") (pin "27") (pinfunction "XIN32_27") (pintype "passive"))
      (node (ref "X2") (pin "2") (pinfunction "OSC2_2") (pintype "passive"))
    )
    (net (code "54") (name "Net-(U8-XOUT32)") (class "Default")
      (node (ref "C10") (pin "1") (pinfunction "1_1") (pintype "passive"))
      (node (ref "U8") (pin "26") (pinfunction "XOUT32_26") (pintype "passive"))
      (node (ref "X2") (pin "1") (pinfunction "OSC1_1") (pintype "passive"))
    )
    (net (code "55") (name "Net-(U10-PROG)") (class "Default")
      (node (ref "R13") (pin "1") (pinfunction "1_1") (pintype "passive"))
      (node (ref "U10") (pin "1") (pinfunction "PROG_1") (pintype "passive"))
    )
    (net (code "56") (name "Net-(U11-CELL)") (class "Default")
      (node (ref "C23") (pin "2") (pinfunction "2_2") (pintype "passive"))
      (node (ref "R4") (pin "1") (pinfunction "1_1") (pintype "passive"))
      (node (ref "U11") (pin "2") (pinfunction "CELL_2") (pintype "passive"))
    )
    (net (code "57") (name "Net-(U11-VDD)") (class "Default")
      (node (ref "C25") (pin "1") (pinfunction "1_1") (pintype "passive"))
      (node (ref "R7") (pin "1") (pinfunction "1_1") (pintype "passive"))
      (node (ref "U11") (pin "3") (pinfunction "VDD_3") (pintype "passive"))
    )
    (net (code "58") (name "Net-(USB1-CC1)") (class "Default")
      (node (ref "R8") (pin "1") (pinfunction "1_1") (pintype "passive"))
      (node (ref "USB1") (pin "A5") (pinfunction "CC1_A5") (pintype "passive"))
    )
    (net (code "59") (name "Net-(USB1-CC2)") (class "Default")
      (node (ref "R9") (pin "2") (pinfunction "2_2") (pintype "passive"))
      (node (ref "USB1") (pin "B5") (pinfunction "CC2_B5") (pintype "passive"))
    )
    (net (code "60") (name "unconnected-(LED4-DOUT-Pad1)") (class "Default")
      (node (ref "LED4") (pin "1") (pinfunction "DOUT_1") (pintype "passive"))
    )
    (net (code "61") (name "unconnected-(U7-INT-Pad2)") (class "Default")
      (node (ref "U7") (pin "2") (pinfunction "INT_2") (pintype "passive"))
    )
    (net (code "62") (name "unconnected-(U8-INT-Pad14)") (class "Default")
      (node (ref "U8") (pin "14") (pinfunction "INT_14") (pintype "passive"))
    )
    (net (code "63") (name "unconnected-(U8-PIN1-Pad1)") (class "Default")
      (node (ref "U8") (pin "1") (pinfunction "PIN1_1") (pintype "passive"))
    )
    (net (code "64") (name "unconnected-(U8-PIN7-Pad7)") (class "Default")
      (node (ref "U8") (pin "7") (pinfunction "PIN7_7") (pintype "passive"))
    )
    (net (code "65") (name "unconnected-(U8-PIN8-Pad8)") (class "Default")
      (node (ref "U8") (pin "8") (pinfunction "PIN8_8") (pintype "passive"))
    )
    (net (code "66") (name "unconnected-(U8-PIN12-Pad12)") (class "Default")
      (node (ref "U8") (pin "12") (pinfunction "PIN12_12") (pintype "passive"))
    )
    (net (code "67") (name "unconnected-(U8-PIN13-Pad13)") (class "Default")
      (node (ref "U8") (pin "13") (pinfunction "PIN13_13") (pintype "passive"))
    )
    (net (code "68") (name "unconnected-(U8-PIN21-Pad21)") (class "Default")
      (node (ref "U8") (pin "21") (pinfunction "PIN21_21") (pintype "passive"))
    )
    (net (code "69") (name "unconnected-(U8-PIN22-Pad22)") (class "Default")
      (node (ref "U8") (pin "22") (pinfunction "PIN22_22") (pintype "passive"))
    )
    (net (code "70") (name "unconnected-(U8-PIN23-Pad23)") (class "Default")
      (node (ref "U8") (pin "23") (pinfunction "PIN23_23") (pintype "passive"))
    )
    (net (code "71") (name "unconnected-(U8-PIN24-Pad24)") (class "Default")
      (node (ref "U8") (pin "24") (pinfunction "PIN24_24") (pintype "passive"))
    )
    (net (code "72") (name "unconnected-(U10-FULL-Pad2)") (class "Default")
      (node (ref "U10") (pin "2") (pinfunction "FULL_2") (pintype "passive"))
    )
    (net (code "73") (name "unconnected-(U11-ALRT--Pad5)") (class "Default")
      (node (ref "U11") (pin "5") (pinfunction "ALRT-_5") (pintype "passive"))
    )
    (net (code "74") (name "unconnected-(USB1-SBU1-PadA8)") (class "Default")
      (node (ref "USB1") (pin "A8") (pinfunction "SBU1_A8") (pintype "passive"))
    )
    (net (code "75") (name "unconnected-(USB1-SBU2-PadB8)") (class "Default")
      (node (ref "USB1") (pin "B8") (pinfunction "SBU2_B8") (pintype "passive"))
    )
  )
)
